# clipper_and_clamper.net
KiCad netlist of a schematic drawn in EAGLE
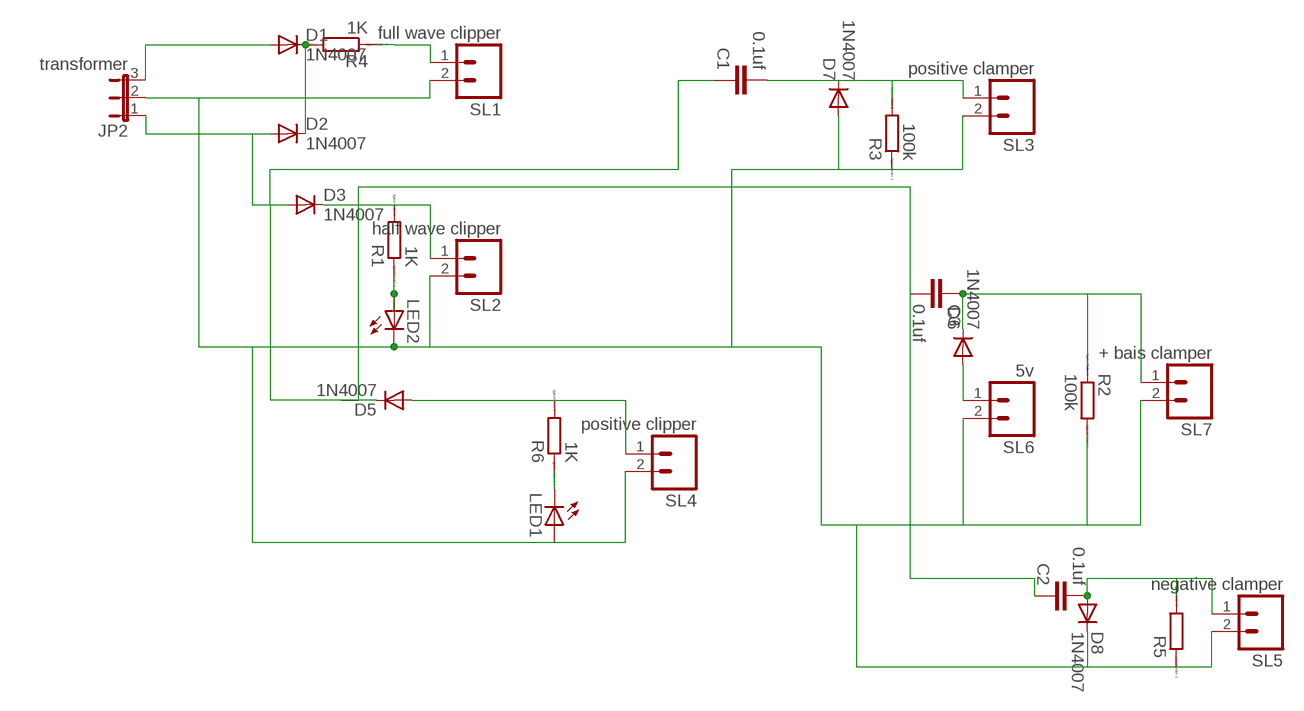
[diagram p0: schematic, sheet 1]

(export (version "E")
  (design (tool "Eeschema 10.0.6"))
  (components
    (comp (ref "C1")
      (value "0.1uf")
      (footprint "eagle-import:C2.5-3")
      (libsource (lib "eagle-import") (part "C2,5-3"))
    )
    (comp (ref "C2")
      (value "0.1uf")
      (footprint "eagle-import:C2.5-3")
      (libsource (lib "eagle-import") (part "C2,5-3"))
    )
    (comp (ref "C3")
      (value "0.1uf")
      (footprint "eagle-import:C2.5-3")
      (libsource (lib "eagle-import") (part "C2,5-3"))
    )
    (comp (ref "D1")
      (value "1N4007")
      (footprint "eagle-import:DO41-10")
      (libsource (lib "eagle-import") (part "1N4004"))
    )
    (comp (ref "D2")
      (value "1N4007")
      (footprint "eagle-import:DO41-10")
      (libsource (lib "eagle-import") (part "1N4004"))
    )
    (comp (ref "D3")
      (value "1N4007")
      (footprint "eagle-import:DO41-10")
      (libsource (lib "eagle-import") (part "1N4004"))
    )
    (comp (ref "D5")
      (value "1N4007")
      (footprint "eagle-import:DO41-10")
      (libsource (lib "eagle-import") (part "1N4004"))
    )
    (comp (ref "D6")
      (value "1N4007")
      (footprint "eagle-import:DO41-10")
      (libsource (lib "eagle-import") (part "1N4004"))
    )
    (comp (ref "D7")
      (value "1N4007")
      (footprint "eagle-import:DO41-10")
      (libsource (lib "eagle-import") (part "1N4004"))
    )
    (comp (ref "D8")
      (value "1N4007")
      (footprint "eagle-import:DO41-10")
      (libsource (lib "eagle-import") (part "1N4004"))
    )
    (comp (ref "JP2")
      (value "transformer")
      (footprint "eagle-import:JP2")
      (libsource (lib "eagle-import") (part "JP2E"))
    )
    (comp (ref "LED1")
      (value "LED3MM")
      (footprint "eagle-import:LED3MM")
      (libsource (lib "eagle-import") (part "LED3MM"))
    )
    (comp (ref "LED2")
      (value "LED3MM")
      (footprint "eagle-import:LED3MM")
      (libsource (lib "eagle-import") (part "LED3MM"))
    )
    (comp (ref "R1")
      (value "1K")
      (footprint "eagle-import:0204_7")
      (libsource (lib "eagle-import") (part "R0204/7"))
    )
    (comp (ref "R2")
      (value "100k")
      (footprint "eagle-import:0204_7")
      (libsource (lib "eagle-import") (part "R0204/7"))
    )
    (comp (ref "R3")
      (value "100k")
      (footprint "eagle-import:0204_7")
      (libsource (lib "eagle-import") (part "R0204/7"))
    )
    (comp (ref "R4")
      (value "1K")
      (footprint "eagle-import:0204_7")
      (libsource (lib "eagle-import") (part "R0204/7"))
    )
    (comp (ref "R5")
      (value "R0204/7")
      (footprint "eagle-import:0204_7")
      (libsource (lib "eagle-import") (part "R0204/7"))
    )
    (comp (ref "R6")
      (value "1K")
      (footprint "eagle-import:0204_7")
      (libsource (lib "eagle-import") (part "R0204/7"))
    )
    (comp (ref "SL1")
      (value "full wave clipper")
      (footprint "eagle-import:02P")
      (libsource (lib "eagle-import") (part "M02"))
    )
    (comp (ref "SL2")
      (value "half wave clipper")
      (footprint "eagle-import:02P")
      (libsource (lib "eagle-import") (part "M02"))
    )
    (comp (ref "SL3")
      (value "positive clamper")
      (footprint "eagle-import:02P")
      (libsource (lib "eagle-import") (part "M02"))
    )
    (comp (ref "SL4")
      (value "positive clipper")
      (footprint "eagle-import:02P")
      (libsource (lib "eagle-import") (part "M02"))
    )
    (comp (ref "SL5")
      (value "negative clamper")
      (footprint "eagle-import:02P")
      (fields (field (name "OC_FARNELL") "unknown") (field (name "OC_NEWARK") "unknown"))
      (libsource (lib "eagle-import") (part "M02"))
    )
    (comp (ref "SL6")
      (value "5v")
      (footprint "eagle-import:02P")
      (libsource (lib "eagle-import") (part "M02"))
    )
    (comp (ref "SL7")
      (value "+ bais clamper")
      (footprint "eagle-import:02P")
      (libsource (lib "eagle-import") (part "M02"))
    )
  )
  (nets
    (net (code "1") (name "Net-(C1-Pad1)") (class "Default")
      (node (ref "C1") (pin "1") (pinfunction "1_1") (pintype "passive"))
      (node (ref "C2") (pin "1") (pinfunction "1_1") (pintype "passive"))
      (node (ref "C3") (pin "2") (pinfunction "2_2") (pintype "passive"))
      (node (ref "D2") (pin "A") (pinfunction "A_A") (pintype "passive"))
      (node (ref "D3") (pin "A") (pinfunction "A_A") (pintype "passive"))
      (node (ref "D5") (pin "C") (pinfunction "C_C") (pintype "passive"))
      (node (ref "JP2") (pin "1") (pinfunction "1_1") (pintype "passive"))
    )
    (net (code "2") (name "Net-(C1-Pad2)") (class "Default")
      (node (ref "C1") (pin "2") (pinfunction "2_2") (pintype "passive"))
      (node (ref "D7") (pin "C") (pinfunction "C_C") (pintype "passive"))
      (node (ref "R3") (pin "2") (pinfunction "2_2") (pintype "passive"))
      (node (ref "SL3") (pin "1") (pinfunction "1_1") (pintype "passive"))
    )
    (net (code "3") (name "Net-(C2-Pad2)") (class "Default")
      (node (ref "C2") (pin "2") (pinfunction "2_2") (pintype "passive"))
      (node (ref "D8") (pin "A") (pinfunction "A_A") (pintype "passive"))
      (node (ref "R5") (pin "2") (pinfunction "2_2") (pintype "passive"))
      (node (ref "SL5") (pin "1") (pinfunction "1_1") (pintype "passive"))
    )
    (net (code "4") (name "Net-(C3-Pad1)") (class "Default")
      (node (ref "C3") (pin "1") (pinfunction "1_1") (pintype "passive"))
      (node (ref "D6") (pin "C") (pinfunction "C_C") (pintype "passive"))
      (node (ref "R2") (pin "1") (pinfunction "1_1") (pintype "passive"))
      (node (ref "SL7") (pin "1") (pinfunction "1_1") (pintype "passive"))
    )
    (net (code "5") (name "Net-(D1-PadA)") (class "Default")
      (node (ref "D1") (pin "A") (pinfunction "A_A") (pintype "passive"))
      (node (ref "JP2") (pin "3") (pinfunction "3_3") (pintype "passive"))
    )
    (net (code "6") (name "Net-(D1-PadC)") (class "Default")
      (node (ref "D1") (pin "C") (pinfunction "C_C") (pintype "passive"))
      (node (ref "D2") (pin "C") (pinfunction "C_C") (pintype "passive"))
      (node (ref "R4") (pin "2") (pinfunction "2_2") (pintype "passive"))
    )
    (net (code "7") (name "Net-(D3-PadC)") (class "Default")
      (node (ref "D3") (pin "C") (pinfunction "C_C") (pintype "passive"))
      (node (ref "R1") (pin "2") (pinfunction "2_2") (pintype "passive"))
      (node (ref "SL2") (pin "1") (pinfunction "1_1") (pintype "passive"))
    )
    (net (code "8") (name "Net-(D5-PadA)") (class "Default")
      (node (ref "D5") (pin "A") (pinfunction "A_A") (pintype "passive"))
      (node (ref "R6") (pin "2") (pinfunction "2_2") (pintype "passive"))
      (node (ref "SL4") (pin "1") (pinfunction "1_1") (pintype "passive"))
    )
    (net (code "9") (name "Net-(D6-PadA)") (class "Default")
      (node (ref "D6") (pin "A") (pinfunction "A_A") (pintype "passive"))
      (node (ref "SL6") (pin "1") (pinfunction "1_1") (pintype "passive"))
    )
    (net (code "10") (name "Net-(LED1-C)") (class "Default")
      (node (ref "LED1") (pin "K") (pinfunction "C_K") (pintype "passive"))
      (node (ref "R6") (pin "1") (pinfunction "1_1") (pintype "passive"))
    )
    (net (code "11") (name "Net-(LED2-C)") (class "Default")
      (node (ref "D7") (pin "A") (pinfunction "A_A") (pintype "passive"))
      (node (ref "D8") (pin "C") (pinfunction "C_C") (pintype "passive"))
      (node (ref "JP2") (pin "2") (pinfunction "2_2") (pintype "passive"))
      (node (ref "LED1") (pin "A") (pinfunction "A_A") (pintype "passive"))
      (node (ref "LED2") (pin "K") (pinfunction "C_K") (pintype "passive"))
      (node (ref "R2") (pin "2") (pinfunction "2_2") (pintype "passive"))
      (node (ref "R3") (pin "1") (pinfunction "1_1") (pintype "passive"))
      (node (ref "R5") (pin "1") (pinfunction "1_1") (pintype "passive"))
      (node (ref "SL1") (pin "2") (pinfunction "2_2") (pintype "passive"))
      (node (ref "SL2") (pin "2") (pinfunction "2_2") (pintype "passive"))
      (node (ref "SL3") (pin "2") (pinfunction "2_2") (pintype "passive"))
      (node (ref "SL4") (pin "2") (pinfunction "2_2") (pintype "passive"))
      (node (ref "SL5") (pin "2") (pinfunction "2_2") (pintype "passive"))
      (node (ref "SL6") (pin "2") (pinfunction "2_2") (pintype "passive"))
      (node (ref "SL7") (pin "2") (pinfunction "2_2") (pintype "passive"))
    )
    (net (code "12") (name "Net-(LED2-PadA)") (class "Default")
      (node (ref "LED2") (pin "A") (pinfunction "A_A") (pintype "passive"))
      (node (ref "R1") (pin "1") (pinfunction "1_1") (pintype "passive"))
    )
    (net (code "13") (name "Net-(R4-Pad1)") (class "Default")
      (node (ref "R4") (pin "1") (pinfunction "1_1") (pintype "passive"))
      (node (ref "SL1") (pin "1") (pinfunction "1_1") (pintype "passive"))
    )
  )
)
